# HABSat2_schematic.net
KiCad netlist of a schematic drawn in EasyEDA
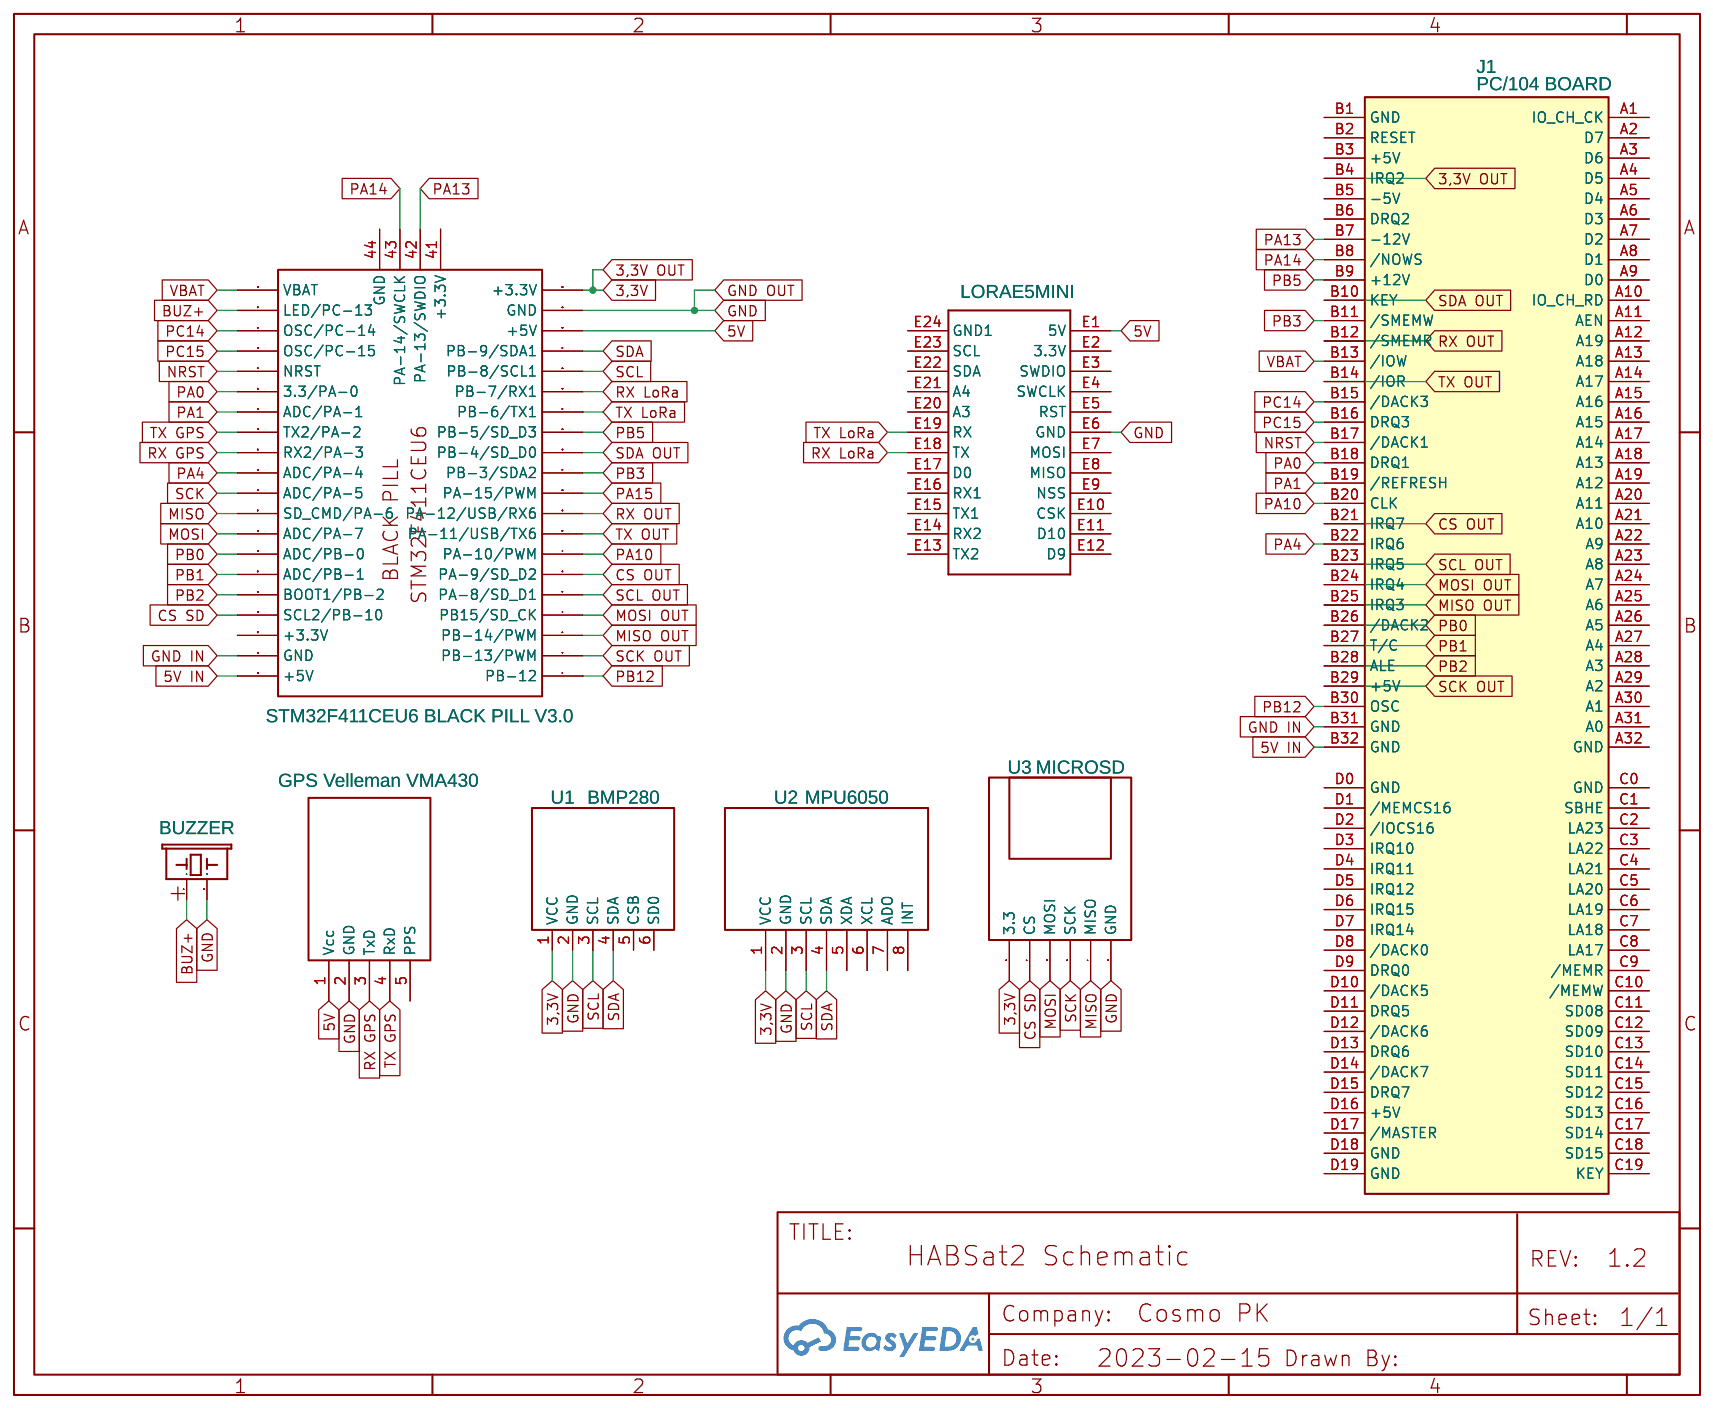
[diagram p0: schematic sheet]

(export (version "E")
  (design (tool "Eeschema 10.0.6"))
  (components
    (comp (ref "1") (value "LORAE5MINI") (libsource (lib "") (part "LORAE5MINI")))
    (comp (ref "J1") (value "PC/104 BOARD") (libsource (lib "") (part "PC/104 BOARD")))
    (comp (ref "SG1") (value "BUZZER") (libsource (lib "") (part "BUZZER KX-12MM")))
    (comp (ref "STM1")
      (value "STM32F411CEU6 BLACK PILL V3.0")
      (libsource (lib "") (part "STM32F411CEU6 BLACK PILL V3.0"))
    )
    (comp (ref "U1")
      (value "BMP280")
      (fields (field (name "BOM_Manufacturer Part") "GY-BMP280"))
      (libsource (lib "") (part "GY-BMP280"))
    )
    (comp (ref "U2") (value "MPU6050") (libsource (lib "") (part "MPU6050")))
    (comp (ref "U3") (value "MICROSD") (libsource (lib "") (part "MICROSD")))
    (comp (ref "VCC")
      (value "GPS Velleman VMA430")
      (fields (field (name "BOM_Manufacturer Part") "VMA430"))
      (libsource (lib "") (part "GPS Velleman VMA430"))
    )
  )
  (nets
    (net (code "1") (name "3,3V") (class "Default")
      (node (ref "J1") (pin "B4") (pinfunction "IRQ2_B4") (pintype "unspecified"))
      (node (ref "STM1") (pin "20") (pinfunction "+3.3V_20") (pintype "unspecified"))
      (node (ref "U1") (pin "1") (pinfunction "VCC_1") (pintype "unspecified"))
      (node (ref "U2") (pin "1") (pinfunction "VCC_1") (pintype "unspecified"))
      (node (ref "U3") (pin "5") (pinfunction "3.3_5") (pintype "unspecified"))
    )
    (net (code "2") (name "5V") (class "Default")
      (node (ref "1") (pin "E1") (pinfunction "5V_E1") (pintype "bidirectional"))
      (node (ref "STM1") (pin "18") (pinfunction "+5V_18") (pintype "unspecified"))
      (node (ref "VCC") (pin "1") (pinfunction "Vcc_1") (pintype "unspecified"))
    )
    (net (code "3") (name "5V IN") (class "Default")
      (node (ref "J1") (pin "B32") (pinfunction "GND_B32") (pintype "bidirectional"))
      (node (ref "STM1") (pin "40") (pinfunction "+5V_40") (pintype "unspecified"))
    )
    (net (code "4") (name "BUZ+") (class "Default")
      (node (ref "SG1") (pin "1") (pinfunction "1_1") (pintype "unspecified"))
      (node (ref "STM1") (pin "22") (pinfunction "LED/PC-13_22") (pintype "unspecified"))
    )
    (net (code "5") (name "CS OUT") (class "Default")
      (node (ref "J1") (pin "B21") (pinfunction "IRQ7_B21") (pintype "unspecified"))
      (node (ref "STM1") (pin "6") (pinfunction "PA-9/SD_D2_6") (pintype "unspecified"))
    )
    (net (code "6") (name "CS SD") (class "Default")
      (node (ref "STM1") (pin "37") (pinfunction "SCL2/PB-10_37") (pintype "unspecified"))
      (node (ref "U3") (pin "1") (pinfunction "CS_1") (pintype "unspecified"))
    )
    (net (code "7") (name "GND") (class "Default")
      (node (ref "1") (pin "E6") (pinfunction "GND_E6") (pintype "bidirectional"))
      (node (ref "SG1") (pin "2") (pinfunction "2_2") (pintype "unspecified"))
      (node (ref "STM1") (pin "19") (pinfunction "GND_19") (pintype "unspecified"))
      (node (ref "U1") (pin "2") (pinfunction "GND_2") (pintype "unspecified"))
      (node (ref "U2") (pin "2") (pinfunction "GND_2") (pintype "unspecified"))
      (node (ref "U3") (pin "6") (pinfunction "GND_6") (pintype "unspecified"))
      (node (ref "VCC") (pin "2") (pinfunction "GND_2") (pintype "unspecified"))
    )
    (net (code "8") (name "GND IN") (class "Default")
      (node (ref "J1") (pin "B31") (pinfunction "GND_B31") (pintype "bidirectional"))
      (node (ref "STM1") (pin "39") (pinfunction "GND_39") (pintype "unspecified"))
    )
    (net (code "9") (name "MISO") (class "Default")
      (node (ref "STM1") (pin "32") (pinfunction "SD_CMD/PA-6_32") (pintype "unspecified"))
      (node (ref "U3") (pin "4") (pinfunction "MISO_4") (pintype "unspecified"))
    )
    (net (code "10") (name "MISO OUT") (class "Default")
      (node (ref "J1") (pin "B25") (pinfunction "IRQ3_B25") (pintype "unspecified"))
      (node (ref "STM1") (pin "3") (pinfunction "PB-14/PWM_3") (pintype "unspecified"))
    )
    (net (code "11") (name "MOSI") (class "Default")
      (node (ref "STM1") (pin "33") (pinfunction "ADC/PA-7_33") (pintype "unspecified"))
      (node (ref "U3") (pin "3") (pinfunction "MOSI_3") (pintype "unspecified"))
    )
    (net (code "12") (name "MOSI OUT") (class "Default")
      (node (ref "J1") (pin "B24") (pinfunction "IRQ4_B24") (pintype "unspecified"))
      (node (ref "STM1") (pin "4") (pinfunction "PB15/SD_CK_4") (pintype "unspecified"))
    )
    (net (code "13") (name "NRST") (class "Default")
      (node (ref "J1") (pin "B17") (pinfunction "/DACK1_B17") (pintype "unspecified"))
      (node (ref "STM1") (pin "25") (pinfunction "NRST_25") (pintype "unspecified"))
    )
    (net (code "14") (name "PA0") (class "Default")
      (node (ref "J1") (pin "B18") (pinfunction "DRQ1_B18") (pintype "unspecified"))
      (node (ref "STM1") (pin "26") (pinfunction "3.3/PA-0_26") (pintype "unspecified"))
    )
    (net (code "15") (name "PA1") (class "Default")
      (node (ref "J1") (pin "B19") (pinfunction "/REFRESH_B19") (pintype "unspecified"))
      (node (ref "STM1") (pin "27") (pinfunction "ADC/PA-1_27") (pintype "unspecified"))
    )
    (net (code "16") (name "PA4") (class "Default")
      (node (ref "J1") (pin "B22") (pinfunction "IRQ6_B22") (pintype "unspecified"))
      (node (ref "STM1") (pin "30") (pinfunction "ADC/PA-4_30") (pintype "unspecified"))
    )
    (net (code "17") (name "PA10") (class "Default")
      (node (ref "J1") (pin "B20") (pinfunction "CLK_B20") (pintype "output"))
      (node (ref "STM1") (pin "7") (pinfunction "PA-10/PWM_7") (pintype "unspecified"))
    )
    (net (code "18") (name "PA13") (class "Default")
      (node (ref "J1") (pin "B7") (pinfunction "-12V_B7") (pintype "bidirectional"))
      (node (ref "STM1") (pin "42") (pinfunction "PA-13/SWDIO_42") (pintype "unspecified"))
    )
    (net (code "19") (name "PA14") (class "Default")
      (node (ref "J1") (pin "B8") (pinfunction "/NOWS_B8") (pintype "unspecified"))
      (node (ref "STM1") (pin "43") (pinfunction "PA-14/SWCLK_43") (pintype "unspecified"))
    )
    (net (code "20") (name "PA15") (class "Default")
      (node (ref "STM1") (pin "10") (pinfunction "PA-15/PWM_10") (pintype "unspecified"))
    )
    (net (code "21") (name "PB0") (class "Default")
      (node (ref "J1") (pin "B26") (pinfunction "/DACK2_B26") (pintype "unspecified"))
      (node (ref "STM1") (pin "34") (pinfunction "ADC/PB-0_34") (pintype "unspecified"))
    )
    (net (code "22") (name "PB1") (class "Default")
      (node (ref "J1") (pin "B27") (pinfunction "T/C_B27") (pintype "unspecified"))
      (node (ref "STM1") (pin "35") (pinfunction "ADC/PB-1_35") (pintype "unspecified"))
    )
    (net (code "23") (name "PB2") (class "Default")
      (node (ref "J1") (pin "B28") (pinfunction "ALE_B28") (pintype "output"))
      (node (ref "STM1") (pin "36") (pinfunction "BOOT1/PB-2_36") (pintype "unspecified"))
    )
    (net (code "24") (name "PB3") (class "Default")
      (node (ref "J1") (pin "B11") (pinfunction "/SMEMW_B11") (pintype "output"))
      (node (ref "STM1") (pin "11") (pinfunction "PB-3/SDA2_11") (pintype "unspecified"))
    )
    (net (code "25") (name "PB5") (class "Default")
      (node (ref "J1") (pin "B9") (pinfunction "+12V_B9") (pintype "bidirectional"))
      (node (ref "STM1") (pin "13") (pinfunction "PB-5/SD_D3_13") (pintype "unspecified"))
    )
    (net (code "26") (name "PB12") (class "Default")
      (node (ref "J1") (pin "B30") (pinfunction "OSC_B30") (pintype "output"))
      (node (ref "STM1") (pin "1") (pinfunction "PB-12_1") (pintype "unspecified"))
    )
    (net (code "27") (name "PC14") (class "Default")
      (node (ref "J1") (pin "B15") (pinfunction "/DACK3_B15") (pintype "unspecified"))
      (node (ref "STM1") (pin "23") (pinfunction "OSC/PC-14_23") (pintype "unspecified"))
    )
    (net (code "28") (name "PC15") (class "Default")
      (node (ref "J1") (pin "B16") (pinfunction "DRQ3_B16") (pintype "unspecified"))
      (node (ref "STM1") (pin "24") (pinfunction "OSC/PC-15_24") (pintype "unspecified"))
    )
    (net (code "29") (name "RX GPS") (class "Default")
      (node (ref "STM1") (pin "29") (pinfunction "RX2/PA-3_29") (pintype "unspecified"))
      (node (ref "VCC") (pin "3") (pinfunction "TxD_3") (pintype "unspecified"))
    )
    (net (code "30") (name "RX LoRa") (class "Default")
      (node (ref "1") (pin "E18") (pinfunction "TX_E18") (pintype "bidirectional"))
      (node (ref "STM1") (pin "15") (pinfunction "PB-7/RX1_15") (pintype "unspecified"))
    )
    (net (code "31") (name "RX OUT") (class "Default")
      (node (ref "J1") (pin "B12") (pinfunction "/SMEMR_B12") (pintype "output"))
      (node (ref "STM1") (pin "9") (pinfunction "PA-12/USB/RX6_9") (pintype "unspecified"))
    )
    (net (code "32") (name "SCK") (class "Default")
      (node (ref "STM1") (pin "31") (pinfunction "ADC/PA-5_31") (pintype "unspecified"))
      (node (ref "U3") (pin "2") (pinfunction "SCK_2") (pintype "unspecified"))
    )
    (net (code "33") (name "SCK OUT") (class "Default")
      (node (ref "J1") (pin "B29") (pinfunction "+5V_B29") (pintype "bidirectional"))
      (node (ref "STM1") (pin "2") (pinfunction "PB-13/PWM_2") (pintype "unspecified"))
    )
    (net (code "34") (name "SCL") (class "Default")
      (node (ref "STM1") (pin "16") (pinfunction "PB-8/SCL1_16") (pintype "unspecified"))
      (node (ref "U1") (pin "3") (pinfunction "SCL_3") (pintype "unspecified"))
      (node (ref "U2") (pin "3") (pinfunction "SCL_3") (pintype "unspecified"))
    )
    (net (code "35") (name "SCL OUT") (class "Default")
      (node (ref "J1") (pin "B23") (pinfunction "IRQ5_B23") (pintype "unspecified"))
      (node (ref "STM1") (pin "5") (pinfunction "PA-8/SD_D1_5") (pintype "unspecified"))
    )
    (net (code "36") (name "SDA") (class "Default")
      (node (ref "STM1") (pin "17") (pinfunction "PB-9/SDA1_17") (pintype "unspecified"))
      (node (ref "U1") (pin "4") (pinfunction "SDA_4") (pintype "unspecified"))
      (node (ref "U2") (pin "4") (pinfunction "SDA_4") (pintype "unspecified"))
    )
    (net (code "37") (name "SDA OUT") (class "Default")
      (node (ref "J1") (pin "B10") (pinfunction "KEY_B10") (pintype "bidirectional"))
      (node (ref "STM1") (pin "12") (pinfunction "PB-4/SD_D0_12") (pintype "unspecified"))
    )
    (net (code "38") (name "TX GPS") (class "Default")
      (node (ref "STM1") (pin "28") (pinfunction "TX2/PA-2_28") (pintype "unspecified"))
      (node (ref "VCC") (pin "4") (pinfunction "RxD_4") (pintype "unspecified"))
    )
    (net (code "39") (name "TX LoRa") (class "Default")
      (node (ref "1") (pin "E19") (pinfunction "RX_E19") (pintype "bidirectional"))
      (node (ref "STM1") (pin "14") (pinfunction "PB-6/TX1_14") (pintype "unspecified"))
    )
    (net (code "40") (name "TX OUT") (class "Default")
      (node (ref "J1") (pin "B14") (pinfunction "/IOR_B14") (pintype "output"))
      (node (ref "STM1") (pin "8") (pinfunction "PA-11/USB/TX6_8") (pintype "unspecified"))
    )
    (net (code "41") (name "VBAT") (class "Default")
      (node (ref "J1") (pin "B13") (pinfunction "/IOW_B13") (pintype "output"))
      (node (ref "STM1") (pin "21") (pinfunction "VBAT_21") (pintype "unspecified"))
    )
    (net (code "42") (name "unconnected-(1-3.3V-PadE2)") (class "Default")
      (node (ref "1") (pin "E2") (pinfunction "3.3V_E2") (pintype "bidirectional"))
    )
    (net (code "43") (name "unconnected-(1-A3-PadE20)") (class "Default")
      (node (ref "1") (pin "E20") (pinfunction "A3_E20") (pintype "bidirectional"))
    )
    (net (code "44") (name "unconnected-(1-A4-PadE21)") (class "Default")
      (node (ref "1") (pin "E21") (pinfunction "A4_E21") (pintype "bidirectional"))
    )
    (net (code "45") (name "unconnected-(1-CSK-PadE10)") (class "Default")
      (node (ref "1") (pin "E10") (pinfunction "CSK_E10") (pintype "bidirectional"))
    )
    (net (code "46") (name "unconnected-(1-D0-PadE17)") (class "Default")
      (node (ref "1") (pin "E17") (pinfunction "D0_E17") (pintype "bidirectional"))
    )
    (net (code "47") (name "unconnected-(1-D9-PadE12)") (class "Default")
      (node (ref "1") (pin "E12") (pinfunction "D9_E12") (pintype "bidirectional"))
    )
    (net (code "48") (name "unconnected-(1-D10-PadE11)") (class "Default")
      (node (ref "1") (pin "E11") (pinfunction "D10_E11") (pintype "bidirectional"))
    )
    (net (code "49") (name "unconnected-(1-GND1-PadE24)") (class "Default")
      (node (ref "1") (pin "E24") (pinfunction "GND1_E24") (pintype "bidirectional"))
    )
    (net (code "50") (name "unconnected-(1-MISO-PadE8)") (class "Default")
      (node (ref "1") (pin "E8") (pinfunction "MISO_E8") (pintype "bidirectional"))
    )
    (net (code "51") (name "unconnected-(1-MOSI-PadE7)") (class "Default")
      (node (ref "1") (pin "E7") (pinfunction "MOSI_E7") (pintype "bidirectional"))
    )
    (net (code "52") (name "unconnected-(1-NSS-PadE9)") (class "Default")
      (node (ref "1") (pin "E9") (pinfunction "NSS_E9") (pintype "bidirectional"))
    )
    (net (code "53") (name "unconnected-(1-RST-PadE5)") (class "Default")
      (node (ref "1") (pin "E5") (pinfunction "RST_E5") (pintype "bidirectional"))
    )
    (net (code "54") (name "unconnected-(1-RX1-PadE16)") (class "Default")
      (node (ref "1") (pin "E16") (pinfunction "RX1_E16") (pintype "bidirectional"))
    )
    (net (code "55") (name "unconnected-(1-RX2-PadE14)") (class "Default")
      (node (ref "1") (pin "E14") (pinfunction "RX2_E14") (pintype "bidirectional"))
    )
    (net (code "56") (name "unconnected-(1-SCL-PadE23)") (class "Default")
      (node (ref "1") (pin "E23") (pinfunction "SCL_E23") (pintype "bidirectional"))
    )
    (net (code "57") (name "unconnected-(1-SDA-PadE22)") (class "Default")
      (node (ref "1") (pin "E22") (pinfunction "SDA_E22") (pintype "bidirectional"))
    )
    (net (code "58") (name "unconnected-(1-SWCLK-PadE4)") (class "Default")
      (node (ref "1") (pin "E4") (pinfunction "SWCLK_E4") (pintype "bidirectional"))
    )
    (net (code "59") (name "unconnected-(1-SWDIO-PadE3)") (class "Default")
      (node (ref "1") (pin "E3") (pinfunction "SWDIO_E3") (pintype "bidirectional"))
    )
    (net (code "60") (name "unconnected-(1-TX1-PadE15)") (class "Default")
      (node (ref "1") (pin "E15") (pinfunction "TX1_E15") (pintype "bidirectional"))
    )
    (net (code "61") (name "unconnected-(1-TX2-PadE13)") (class "Default")
      (node (ref "1") (pin "E13") (pinfunction "TX2_E13") (pintype "bidirectional"))
    )
    (net (code "62") (name "unconnected-(J1-+5V-PadB3)") (class "Default")
      (node (ref "J1") (pin "B3") (pinfunction "+5V_B3") (pintype "bidirectional"))
    )
    (net (code "63") (name "unconnected-(J1-+5V-PadD16)") (class "Default")
      (node (ref "J1") (pin "D16") (pinfunction "+5V_D16") (pintype "bidirectional"))
    )
    (net (code "64") (name "unconnected-(J1--5V-PadB5)") (class "Default")
      (node (ref "J1") (pin "B5") (pinfunction "-5V_B5") (pintype "bidirectional"))
    )
    (net (code "65") (name "unconnected-(J1-A0-PadA31)") (class "Default")
      (node (ref "J1") (pin "A31") (pinfunction "A0_A31") (pintype "bidirectional"))
    )
    (net (code "66") (name "unconnected-(J1-A1-PadA30)") (class "Default")
      (node (ref "J1") (pin "A30") (pinfunction "A1_A30") (pintype "bidirectional"))
    )
    (net (code "67") (name "unconnected-(J1-A2-PadA29)") (class "Default")
      (node (ref "J1") (pin "A29") (pinfunction "A2_A29") (pintype "bidirectional"))
    )
    (net (code "68") (name "unconnected-(J1-A3-PadA28)") (class "Default")
      (node (ref "J1") (pin "A28") (pinfunction "A3_A28") (pintype "bidirectional"))
    )
    (net (code "69") (name "unconnected-(J1-A4-PadA27)") (class "Default")
      (node (ref "J1") (pin "A27") (pinfunction "A4_A27") (pintype "bidirectional"))
    )
    (net (code "70") (name "unconnected-(J1-A5-PadA26)") (class "Default")
      (node (ref "J1") (pin "A26") (pinfunction "A5_A26") (pintype "bidirectional"))
    )
    (net (code "71") (name "unconnected-(J1-A6-PadA25)") (class "Default")
      (node (ref "J1") (pin "A25") (pinfunction "A6_A25") (pintype "bidirectional"))
    )
    (net (code "72") (name "unconnected-(J1-A7-PadA24)") (class "Default")
      (node (ref "J1") (pin "A24") (pinfunction "A7_A24") (pintype "bidirectional"))
    )
    (net (code "73") (name "unconnected-(J1-A8-PadA23)") (class "Default")
      (node (ref "J1") (pin "A23") (pinfunction "A8_A23") (pintype "bidirectional"))
    )
    (net (code "74") (name "unconnected-(J1-A9-PadA22)") (class "Default")
      (node (ref "J1") (pin "A22") (pinfunction "A9_A22") (pintype "bidirectional"))
    )
    (net (code "75") (name "unconnected-(J1-A10-PadA21)") (class "Default")
      (node (ref "J1") (pin "A21") (pinfunction "A10_A21") (pintype "bidirectional"))
    )
    (net (code "76") (name "unconnected-(J1-A11-PadA20)") (class "Default")
      (node (ref "J1") (pin "A20") (pinfunction "A11_A20") (pintype "bidirectional"))
    )
    (net (code "77") (name "unconnected-(J1-A12-PadA19)") (class "Default")
      (node (ref "J1") (pin "A19") (pinfunction "A12_A19") (pintype "bidirectional"))
    )
    (net (code "78") (name "unconnected-(J1-A13-PadA18)") (class "Default")
      (node (ref "J1") (pin "A18") (pinfunction "A13_A18") (pintype "bidirectional"))
    )
    (net (code "79") (name "unconnected-(J1-A14-PadA17)") (class "Default")
      (node (ref "J1") (pin "A17") (pinfunction "A14_A17") (pintype "bidirectional"))
    )
    (net (code "80") (name "unconnected-(J1-A15-PadA16)") (class "Default")
      (node (ref "J1") (pin "A16") (pinfunction "A15_A16") (pintype "bidirectional"))
    )
    (net (code "81") (name "unconnected-(J1-A16-PadA15)") (class "Default")
      (node (ref "J1") (pin "A15") (pinfunction "A16_A15") (pintype "bidirectional"))
    )
    (net (code "82") (name "unconnected-(J1-A17-PadA14)") (class "Default")
      (node (ref "J1") (pin "A14") (pinfunction "A17_A14") (pintype "bidirectional"))
    )
    (net (code "83") (name "unconnected-(J1-A18-PadA13)") (class "Default")
      (node (ref "J1") (pin "A13") (pinfunction "A18_A13") (pintype "bidirectional"))
    )
    (net (code "84") (name "unconnected-(J1-A19-PadA12)") (class "Default")
      (node (ref "J1") (pin "A12") (pinfunction "A19_A12") (pintype "bidirectional"))
    )
    (net (code "85") (name "unconnected-(J1-AEN-PadA11)") (class "Default")
      (node (ref "J1") (pin "A11") (pinfunction "AEN_A11") (pintype "output"))
    )
    (net (code "86") (name "unconnected-(J1-D0-PadA9)") (class "Default")
      (node (ref "J1") (pin "A9") (pinfunction "D0_A9") (pintype "bidirectional"))
    )
    (net (code "87") (name "unconnected-(J1-D1-PadA8)") (class "Default")
      (node (ref "J1") (pin "A8") (pinfunction "D1_A8") (pintype "bidirectional"))
    )
    (net (code "88") (name "unconnected-(J1-D2-PadA7)") (class "Default")
      (node (ref "J1") (pin "A7") (pinfunction "D2_A7") (pintype "bidirectional"))
    )
    (net (code "89") (name "unconnected-(J1-D3-PadA6)") (class "Default")
      (node (ref "J1") (pin "A6") (pinfunction "D3_A6") (pintype "bidirectional"))
    )
    (net (code "90") (name "unconnected-(J1-D4-PadA5)") (class "Default")
      (node (ref "J1") (pin "A5") (pinfunction "D4_A5") (pintype "bidirectional"))
    )
    (net (code "91") (name "unconnected-(J1-D5-PadA4)") (class "Default")
      (node (ref "J1") (pin "A4") (pinfunction "D5_A4") (pintype "bidirectional"))
    )
    (net (code "92") (name "unconnected-(J1-D6-PadA3)") (class "Default")
      (node (ref "J1") (pin "A3") (pinfunction "D6_A3") (pintype "bidirectional"))
    )
    (net (code "93") (name "unconnected-(J1-D7-PadA2)") (class "Default")
      (node (ref "J1") (pin "A2") (pinfunction "D7_A2") (pintype "bidirectional"))
    )
    (net (code "94") (name "unconnected-(J1-DRQ0-PadD9)") (class "Default")
      (node (ref "J1") (pin "D9") (pinfunction "DRQ0_D9") (pintype "unspecified"))
    )
    (net (code "95") (name "unconnected-(J1-DRQ2-PadB6)") (class "Default")
      (node (ref "J1") (pin "B6") (pinfunction "DRQ2_B6") (pintype "unspecified"))
    )
    (net (code "96") (name "unconnected-(J1-DRQ5-PadD11)") (class "Default")
      (node (ref "J1") (pin "D11") (pinfunction "DRQ5_D11") (pintype "unspecified"))
    )
    (net (code "97") (name "unconnected-(J1-DRQ6-PadD13)") (class "Default")
      (node (ref "J1") (pin "D13") (pinfunction "DRQ6_D13") (pintype "unspecified"))
    )
    (net (code "98") (name "unconnected-(J1-DRQ7-PadD15)") (class "Default")
      (node (ref "J1") (pin "D15") (pinfunction "DRQ7_D15") (pintype "unspecified"))
    )
    (net (code "99") (name "unconnected-(J1-GND-PadA32)") (class "Default")
      (node (ref "J1") (pin "A32") (pinfunction "GND_A32") (pintype "bidirectional"))
    )
    (net (code "100") (name "unconnected-(J1-GND-PadB1)") (class "Default")
      (node (ref "J1") (pin "B1") (pinfunction "GND_B1") (pintype "bidirectional"))
    )
    (net (code "101") (name "unconnected-(J1-GND-PadC0)") (class "Default")
      (node (ref "J1") (pin "C0") (pinfunction "GND_C0") (pintype "unspecified"))
    )
    (net (code "102") (name "unconnected-(J1-GND-PadD0)") (class "Default")
      (node (ref "J1") (pin "D0") (pinfunction "GND_D0") (pintype "unspecified"))
    )
    (net (code "103") (name "unconnected-(J1-GND-PadD18)") (class "Default")
      (node (ref "J1") (pin "D18") (pinfunction "GND_D18") (pintype "bidirectional"))
    )
    (net (code "104") (name "unconnected-(J1-GND-PadD19)") (class "Default")
      (node (ref "J1") (pin "D19") (pinfunction "GND_D19") (pintype "bidirectional"))
    )
    (net (code "105") (name "unconnected-(J1-IO_CH_CK-PadA1)") (class "Default")
      (node (ref "J1") (pin "A1") (pinfunction "IO_CH_CK_A1") (pintype "unspecified"))
    )
    (net (code "106") (name "unconnected-(J1-IO_CH_RD-PadA10)") (class "Default")
      (node (ref "J1") (pin "A10") (pinfunction "IO_CH_RD_A10") (pintype "unspecified"))
    )
    (net (code "107") (name "unconnected-(J1-IRQ10-PadD3)") (class "Default")
      (node (ref "J1") (pin "D3") (pinfunction "IRQ10_D3") (pintype "unspecified"))
    )
    (net (code "108") (name "unconnected-(J1-IRQ11-PadD4)") (class "Default")
      (node (ref "J1") (pin "D4") (pinfunction "IRQ11_D4") (pintype "unspecified"))
    )
    (net (code "109") (name "unconnected-(J1-IRQ12-PadD5)") (class "Default")
      (node (ref "J1") (pin "D5") (pinfunction "IRQ12_D5") (pintype "unspecified"))
    )
    (net (code "110") (name "unconnected-(J1-IRQ14-PadD7)") (class "Default")
      (node (ref "J1") (pin "D7") (pinfunction "IRQ14_D7") (pintype "unspecified"))
    )
    (net (code "111") (name "unconnected-(J1-IRQ15-PadD6)") (class "Default")
      (node (ref "J1") (pin "D6") (pinfunction "IRQ15_D6") (pintype "unspecified"))
    )
    (net (code "112") (name "unconnected-(J1-KEY-PadC19)") (class "Default")
      (node (ref "J1") (pin "C19") (pinfunction "KEY_C19") (pintype "bidirectional"))
    )
    (net (code "113") (name "unconnected-(J1-LA17-PadC8)") (class "Default")
      (node (ref "J1") (pin "C8") (pinfunction "LA17_C8") (pintype "unspecified"))
    )
    (net (code "114") (name "unconnected-(J1-LA18-PadC7)") (class "Default")
      (node (ref "J1") (pin "C7") (pinfunction "LA18_C7") (pintype "unspecified"))
    )
    (net (code "115") (name "unconnected-(J1-LA19-PadC6)") (class "Default")
      (node (ref "J1") (pin "C6") (pinfunction "LA19_C6") (pintype "unspecified"))
    )
    (net (code "116") (name "unconnected-(J1-LA20-PadC5)") (class "Default")
      (node (ref "J1") (pin "C5") (pinfunction "LA20_C5") (pintype "unspecified"))
    )
    (net (code "117") (name "unconnected-(J1-LA21-PadC4)") (class "Default")
      (node (ref "J1") (pin "C4") (pinfunction "LA21_C4") (pintype "unspecified"))
    )
    (net (code "118") (name "unconnected-(J1-LA22-PadC3)") (class "Default")
      (node (ref "J1") (pin "C3") (pinfunction "LA22_C3") (pintype "unspecified"))
    )
    (net (code "119") (name "unconnected-(J1-LA23-PadC2)") (class "Default")
      (node (ref "J1") (pin "C2") (pinfunction "LA23_C2") (pintype "unspecified"))
    )
    (net (code "120") (name "unconnected-(J1-RESET-PadB2)") (class "Default")
      (node (ref "J1") (pin "B2") (pinfunction "RESET_B2") (pintype "output"))
    )
    (net (code "121") (name "unconnected-(J1-SBHE-PadC1)") (class "Default")
      (node (ref "J1") (pin "C1") (pinfunction "SBHE_C1") (pintype "unspecified"))
    )
    (net (code "122") (name "unconnected-(J1-SD08-PadC11)") (class "Default")
      (node (ref "J1") (pin "C11") (pinfunction "SD08_C11") (pintype "bidirectional"))
    )
    (net (code "123") (name "unconnected-(J1-SD09-PadC12)") (class "Default")
      (node (ref "J1") (pin "C12") (pinfunction "SD09_C12") (pintype "bidirectional"))
    )
    (net (code "124") (name "unconnected-(J1-SD10-PadC13)") (class "Default")
      (node (ref "J1") (pin "C13") (pinfunction "SD10_C13") (pintype "bidirectional"))
    )
    (net (code "125") (name "unconnected-(J1-SD11-PadC14)") (class "Default")
      (node (ref "J1") (pin "C14") (pinfunction "SD11_C14") (pintype "bidirectional"))
    )
    (net (code "126") (name "unconnected-(J1-SD12-PadC15)") (class "Default")
      (node (ref "J1") (pin "C15") (pinfunction "SD12_C15") (pintype "bidirectional"))
    )
    (net (code "127") (name "unconnected-(J1-SD13-PadC16)") (class "Default")
      (node (ref "J1") (pin "C16") (pinfunction "SD13_C16") (pintype "bidirectional"))
    )
    (net (code "128") (name "unconnected-(J1-SD14-PadC17)") (class "Default")
      (node (ref "J1") (pin "C17") (pinfunction "SD14_C17") (pintype "bidirectional"))
    )
    (net (code "129") (name "unconnected-(J1-SD15-PadC18)") (class "Default")
      (node (ref "J1") (pin "C18") (pinfunction "SD15_C18") (pintype "bidirectional"))
    )
    (net (code "130") (name "unconnected-(J1-{slash}DACK0-PadD8)") (class "Default")
      (node (ref "J1") (pin "D8") (pinfunction "/DACK0_D8") (pintype "output"))
    )
    (net (code "131") (name "unconnected-(J1-{slash}DACK5-PadD10)") (class "Default")
      (node (ref "J1") (pin "D10") (pinfunction "/DACK5_D10") (pintype "output"))
    )
    (net (code "132") (name "unconnected-(J1-{slash}DACK6-PadD12)") (class "Default")
      (node (ref "J1") (pin "D12") (pinfunction "/DACK6_D12") (pintype "output"))
    )
    (net (code "133") (name "unconnected-(J1-{slash}DACK7-PadD14)") (class "Default")
      (node (ref "J1") (pin "D14") (pinfunction "/DACK7_D14") (pintype "output"))
    )
    (net (code "134") (name "unconnected-(J1-{slash}IOCS16-PadD2)") (class "Default")
      (node (ref "J1") (pin "D2") (pinfunction "/IOCS16_D2") (pintype "unspecified"))
    )
    (net (code "135") (name "unconnected-(J1-{slash}MASTER-PadD17)") (class "Default")
      (node (ref "J1") (pin "D17") (pinfunction "/MASTER_D17") (pintype "unspecified"))
    )
    (net (code "136") (name "unconnected-(J1-{slash}MEMCS16-PadD1)") (class "Default")
      (node (ref "J1") (pin "D1") (pinfunction "/MEMCS16_D1") (pintype "unspecified"))
    )
    (net (code "137") (name "unconnected-(J1-{slash}MEMR-PadC9)") (class "Default")
      (node (ref "J1") (pin "C9") (pinfunction "/MEMR_C9") (pintype "output"))
    )
    (net (code "138") (name "unconnected-(J1-{slash}MEMW-PadC10)") (class "Default")
      (node (ref "J1") (pin "C10") (pinfunction "/MEMW_C10") (pintype "output"))
    )
    (net (code "139") (name "unconnected-(STM1-+3.3V-Pad38)") (class "Default")
      (node (ref "STM1") (pin "38") (pinfunction "+3.3V_38") (pintype "unspecified"))
    )
    (net (code "140") (name "unconnected-(STM1-+3.3V-Pad41)") (class "Default")
      (node (ref "STM1") (pin "41") (pinfunction "+3.3V_41") (pintype "unspecified"))
    )
    (net (code "141") (name "unconnected-(STM1-GND-Pad44)") (class "Default")
      (node (ref "STM1") (pin "44") (pinfunction "GND_44") (pintype "unspecified"))
    )
    (net (code "142") (name "unconnected-(U1-CSB-Pad5)") (class "Default")
      (node (ref "U1") (pin "5") (pinfunction "CSB_5") (pintype "unspecified"))
    )
    (net (code "143") (name "unconnected-(U1-SD0-Pad6)") (class "Default")
      (node (ref "U1") (pin "6") (pinfunction "SD0_6") (pintype "unspecified"))
    )
    (net (code "144") (name "unconnected-(U2-ADO-Pad7)") (class "Default")
      (node (ref "U2") (pin "7") (pinfunction "ADO_7") (pintype "unspecified"))
    )
    (net (code "145") (name "unconnected-(U2-INT-Pad8)") (class "Default")
      (node (ref "U2") (pin "8") (pinfunction "INT_8") (pintype "unspecified"))
    )
    (net (code "146") (name "unconnected-(U2-XCL-Pad6)") (class "Default")
      (node (ref "U2") (pin "6") (pinfunction "XCL_6") (pintype "unspecified"))
    )
    (net (code "147") (name "unconnected-(U2-XDA-Pad5)") (class "Default")
      (node (ref "U2") (pin "5") (pinfunction "XDA_5") (pintype "unspecified"))
    )
    (net (code "148") (name "unconnected-(VCC-PPS-Pad5)") (class "Default")
      (node (ref "VCC") (pin "5") (pinfunction "PPS_5") (pintype "unspecified"))
    )
  )
)
